# 3_Phase_Controller_V0_3.net
KiCad netlist of a schematic drawn in EAGLE
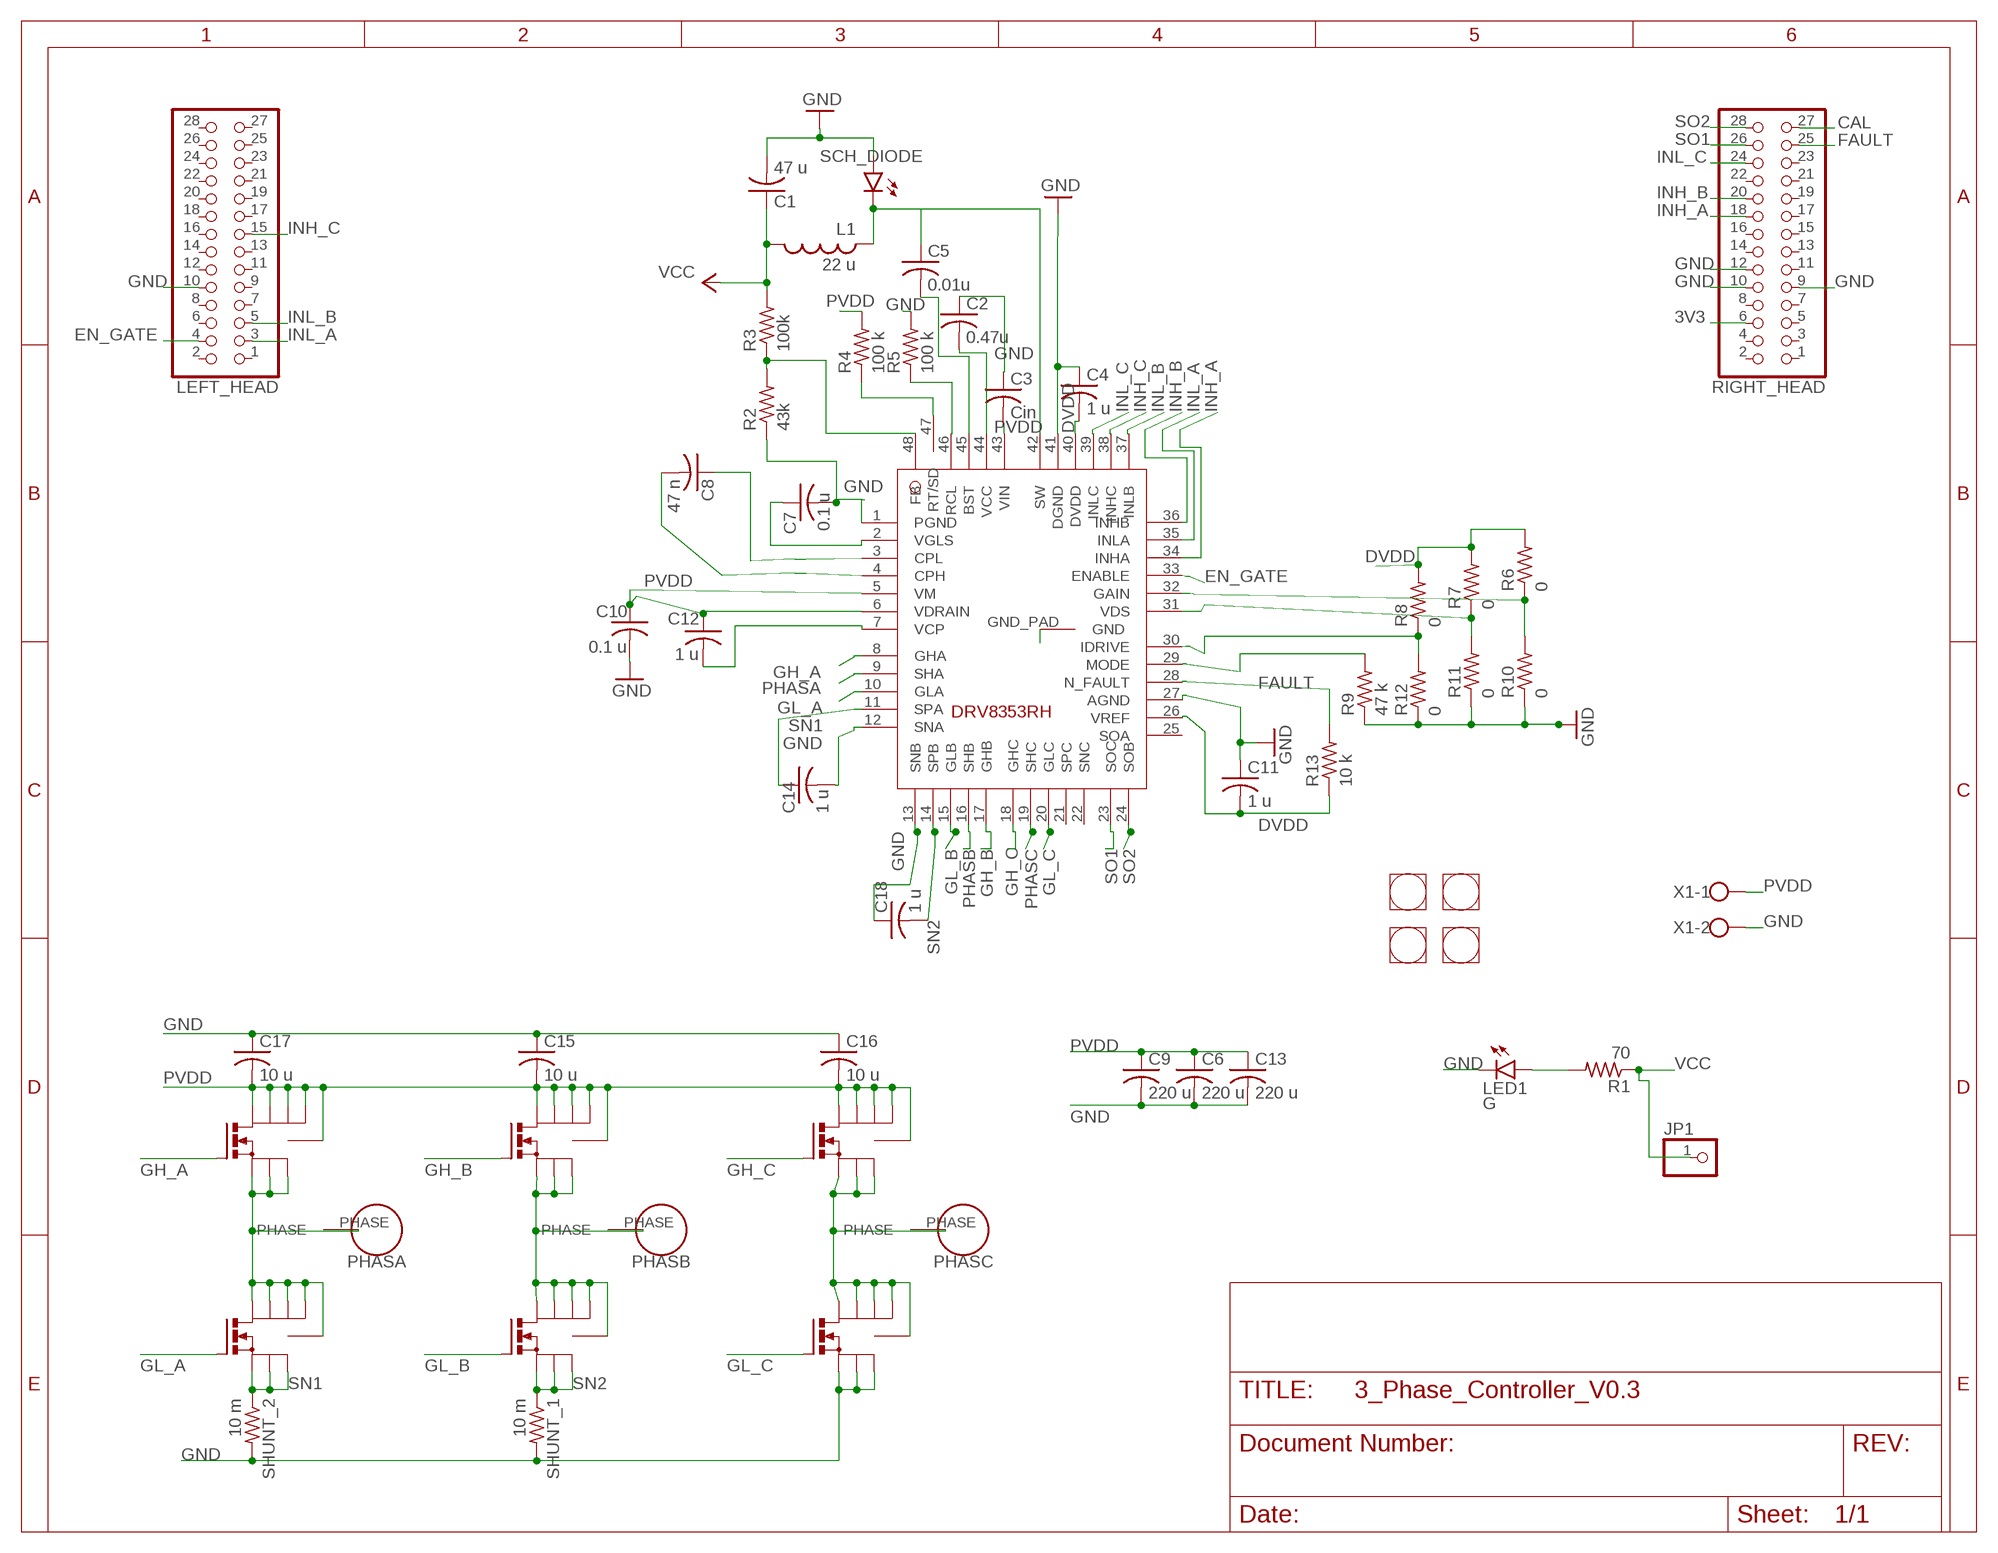
[diagram p0: schematic, sheet 1]

(export (version "E")
  (design (tool "Eeschema 10.0.6"))
  (components
    (comp (ref "A_H")
      (value "SIR178DP")
      (footprint "eagle-import:POWERPAK_SO-8_SINGLE")
      (libsource (lib "eagle-import") (part "SIR178DP"))
    )
    (comp (ref "A_L")
      (value "SIR178DP")
      (footprint "eagle-import:POWERPAK_SO-8_SINGLE")
      (libsource (lib "eagle-import") (part "SIR178DP"))
    )
    (comp (ref "B_H")
      (value "SIR178DP")
      (footprint "eagle-import:POWERPAK_SO-8_SINGLE")
      (libsource (lib "eagle-import") (part "SIR178DP"))
    )
    (comp (ref "B_L")
      (value "SIR178DP")
      (footprint "eagle-import:POWERPAK_SO-8_SINGLE")
      (libsource (lib "eagle-import") (part "SIR178DP"))
    )
    (comp (ref "C1")
      (value "47 u")
      (footprint "eagle-import:C025-024X044")
      (libsource (lib "eagle-import") (part "C-US025-024X044"))
    )
    (comp (ref "C2")
      (value "0.47u")
      (footprint "eagle-import:C0805")
      (libsource (lib "eagle-import") (part "C-USC0805"))
    )
    (comp (ref "C3")
      (value "Cin")
      (footprint "eagle-import:C0805")
      (libsource (lib "eagle-import") (part "C-USC0805"))
    )
    (comp (ref "C4")
      (value "1 u")
      (footprint "eagle-import:C0805")
      (libsource (lib "eagle-import") (part "C-USC0805"))
    )
    (comp (ref "C5")
      (value "0.01u")
      (footprint "eagle-import:C0805")
      (libsource (lib "eagle-import") (part "C-USC0805"))
    )
    (comp (ref "C6")
      (value "220 u")
      (footprint "eagle-import:C050-045X075")
      (libsource (lib "eagle-import") (part "C-US050-045X075"))
    )
    (comp (ref "C7")
      (value "0.1 u")
      (footprint "eagle-import:C0805")
      (libsource (lib "eagle-import") (part "C-USC0805"))
    )
    (comp (ref "C8")
      (value "47 n")
      (footprint "eagle-import:C0805")
      (libsource (lib "eagle-import") (part "C-USC0805"))
    )
    (comp (ref "C9")
      (value "220 u")
      (footprint "eagle-import:C050-045X075")
      (libsource (lib "eagle-import") (part "C-US050-045X075"))
    )
    (comp (ref "C10")
      (value "0.1 u")
      (footprint "eagle-import:C0805")
      (libsource (lib "eagle-import") (part "C-USC0805"))
    )
    (comp (ref "C11")
      (value "1 u")
      (footprint "eagle-import:C0805")
      (libsource (lib "eagle-import") (part "C-USC0805"))
    )
    (comp (ref "C12")
      (value "1 u")
      (footprint "eagle-import:C0805")
      (libsource (lib "eagle-import") (part "C-USC0805"))
    )
    (comp (ref "C13")
      (value "220 u")
      (footprint "eagle-import:C050-045X075")
      (libsource (lib "eagle-import") (part "C-US050-045X075"))
    )
    (comp (ref "C14")
      (value "1 u")
      (footprint "eagle-import:C0805")
      (libsource (lib "eagle-import") (part "C-USC0805"))
    )
    (comp (ref "C15")
      (value "10 u")
      (footprint "eagle-import:C1206")
      (libsource (lib "eagle-import") (part "C-USC1206"))
    )
    (comp (ref "C16")
      (value "10 u")
      (footprint "eagle-import:C1206")
      (libsource (lib "eagle-import") (part "C-USC1206"))
    )
    (comp (ref "C17")
      (value "10 u")
      (footprint "eagle-import:C1206")
      (libsource (lib "eagle-import") (part "C-USC1206"))
    )
    (comp (ref "C18")
      (value "1 u")
      (footprint "eagle-import:C0805")
      (libsource (lib "eagle-import") (part "C-USC0805"))
    )
    (comp (ref "C_H")
      (value "SIR178DP")
      (footprint "eagle-import:POWERPAK_SO-8_SINGLE")
      (libsource (lib "eagle-import") (part "SIR178DP"))
    )
    (comp (ref "C_L")
      (value "SIR178DP")
      (footprint "eagle-import:POWERPAK_SO-8_SINGLE")
      (libsource (lib "eagle-import") (part "SIR178DP"))
    )
    (comp (ref "JP1")
      (value "PINHD-1X1")
      (footprint "eagle-import:1X01")
      (libsource (lib "eagle-import") (part "PINHD-1X1"))
    )
    (comp (ref "L1")
      (value "22 u")
      (footprint "eagle-import:L3225M")
      (libsource (lib "eagle-import") (part "L-USL3225M"))
    )
    (comp (ref "LED1")
      (value "G")
      (footprint "eagle-import:SML0805")
      (libsource (lib "eagle-import") (part "LEDSML0805"))
    )
    (comp (ref "LEFT_HEAD")
      (value "PINHD-2X14")
      (footprint "eagle-import:2X14")
      (libsource (lib "eagle-import") (part "PINHD-2X14"))
    )
    (comp (ref "PHASE_A")
      (value "PHASE_HOLE_V_0.2")
      (footprint "eagle-import:HOLE_V_0.2")
      (libsource (lib "eagle-import") (part "PHASE_HOLE_V_0.2"))
    )
    (comp (ref "PHASE_B")
      (value "PHASE_HOLE_V_0.2")
      (footprint "eagle-import:HOLE_V_0.2")
      (libsource (lib "eagle-import") (part "PHASE_HOLE_V_0.2"))
    )
    (comp (ref "PHASE_C")
      (value "PHASE_HOLE_V_0.2")
      (footprint "eagle-import:HOLE_V_0.2")
      (libsource (lib "eagle-import") (part "PHASE_HOLE_V_0.2"))
    )
    (comp (ref "R1")
      (value "70")
      (footprint "eagle-import:R0805")
      (libsource (lib "eagle-import") (part "R-US_R0805"))
    )
    (comp (ref "R2")
      (value "43k")
      (footprint "eagle-import:R0603")
      (libsource (lib "eagle-import") (part "R-US_R0603"))
    )
    (comp (ref "R3")
      (value "100k")
      (footprint "eagle-import:R0603")
      (libsource (lib "eagle-import") (part "R-US_R0603"))
    )
    (comp (ref "R4")
      (value "100 k")
      (footprint "eagle-import:R0805")
      (libsource (lib "eagle-import") (part "R-US_R0805"))
    )
    (comp (ref "R5")
      (value "100 k")
      (footprint "eagle-import:R0805")
      (libsource (lib "eagle-import") (part "R-US_R0805"))
    )
    (comp (ref "R6")
      (value "0")
      (footprint "eagle-import:R0603")
      (libsource (lib "eagle-import") (part "R-US_R0603"))
    )
    (comp (ref "R7")
      (value "0")
      (footprint "eagle-import:R0603")
      (libsource (lib "eagle-import") (part "R-US_R0603"))
    )
    (comp (ref "R8")
      (value "0")
      (footprint "eagle-import:R0603")
      (libsource (lib "eagle-import") (part "R-US_R0603"))
    )
    (comp (ref "R9")
      (value "47 k")
      (footprint "eagle-import:R0603")
      (libsource (lib "eagle-import") (part "R-US_R0603"))
    )
    (comp (ref "R10")
      (value "0")
      (footprint "eagle-import:R0603")
      (libsource (lib "eagle-import") (part "R-US_R0603"))
    )
    (comp (ref "R11")
      (value "0")
      (footprint "eagle-import:R0603")
      (libsource (lib "eagle-import") (part "R-US_R0603"))
    )
    (comp (ref "R12")
      (value "0")
      (footprint "eagle-import:R0603")
      (libsource (lib "eagle-import") (part "R-US_R0603"))
    )
    (comp (ref "R13")
      (value "10 k")
      (footprint "eagle-import:R0603")
      (libsource (lib "eagle-import") (part "R-US_R0603"))
    )
    (comp (ref "RIGHT_HEAD")
      (value "PINHD-2X14")
      (footprint "eagle-import:2X14")
      (libsource (lib "eagle-import") (part "PINHD-2X14"))
    )
    (comp (ref "SCH_DIODE")
      (value "LEDCHIP-LED0805")
      (footprint "eagle-import:CHIP-LED0805")
      (libsource (lib "eagle-import") (part "LEDCHIP-LED0805"))
    )
    (comp (ref "SHUNT_1")
      (value "10 m")
      (footprint "eagle-import:R2512")
      (libsource (lib "eagle-import") (part "R-US_R2512"))
    )
    (comp (ref "SHUNT_2")
      (value "10 m")
      (footprint "eagle-import:R2512")
      (libsource (lib "eagle-import") (part "R-US_R2512"))
    )
    (comp (ref "U$1")
      (value "STANDOFF")
      (footprint "eagle-import:STANDOFF")
      (libsource (lib "eagle-import") (part "STANDOFF"))
    )
    (comp (ref "U$2")
      (value "STANDOFF")
      (footprint "eagle-import:STANDOFF")
      (libsource (lib "eagle-import") (part "STANDOFF"))
    )
    (comp (ref "U$3")
      (value "DRV8353RH")
      (footprint "eagle-import:VQFN-RGZ0048A")
      (libsource (lib "eagle-import") (part "DRV8353RH"))
    )
    (comp (ref "U$4")
      (value "STANDOFF")
      (footprint "eagle-import:STANDOFF")
      (libsource (lib "eagle-import") (part "STANDOFF"))
    )
    (comp (ref "U$5")
      (value "STANDOFF")
      (footprint "eagle-import:STANDOFF")
      (libsource (lib "eagle-import") (part "STANDOFF"))
    )
    (comp (ref "X1")
      (value "W237-102")
      (footprint "eagle-import:W237-102")
      (fields (field (name "MPN") "237-102"))
      (libsource (lib "eagle-import") (part "W237-102"))
    )
  )
  (nets
    (net (code "1") (name "/3V3") (class "Default")
      (node (ref "RIGHT_HEAD") (pin "6") (pinfunction "6_6") (pintype "passive"))
    )
    (net (code "2") (name "/CAL") (class "Default")
      (node (ref "RIGHT_HEAD") (pin "27") (pinfunction "27_27") (pintype "passive"))
    )
    (net (code "3") (name "/DVDD") (class "Default")
      (node (ref "C11") (pin "2") (pinfunction "2_2") (pintype "passive"))
      (node (ref "C4") (pin "2") (pinfunction "2_2") (pintype "passive"))
      (node (ref "R13") (pin "1") (pinfunction "1_1") (pintype "passive"))
      (node (ref "R6") (pin "2") (pinfunction "2_2") (pintype "passive"))
      (node (ref "R7") (pin "2") (pinfunction "2_2") (pintype "passive"))
      (node (ref "R8") (pin "2") (pinfunction "2_2") (pintype "passive"))
      (node (ref "U$3") (pin "26") (pinfunction "VREF_26") (pintype "bidirectional"))
      (node (ref "U$3") (pin "40") (pinfunction "DVDD_40") (pintype "bidirectional"))
    )
    (net (code "4") (name "/EN_GATE") (class "Default")
      (node (ref "LEFT_HEAD") (pin "4") (pinfunction "4_4") (pintype "passive"))
      (node (ref "U$3") (pin "33") (pinfunction "ENABLE_33") (pintype "bidirectional"))
    )
    (net (code "5") (name "/FAULT") (class "Default")
      (node (ref "R13") (pin "2") (pinfunction "2_2") (pintype "passive"))
      (node (ref "RIGHT_HEAD") (pin "25") (pinfunction "25_25") (pintype "passive"))
      (node (ref "U$3") (pin "28") (pinfunction "N_FAULT_28") (pintype "bidirectional"))
    )
    (net (code "6") (name "/GH_A") (class "Default")
      (node (ref "A_H") (pin "GATE") (pinfunction "G_GATE") (pintype "passive"))
      (node (ref "U$3") (pin "8") (pinfunction "GHA_8") (pintype "bidirectional"))
    )
    (net (code "7") (name "/GH_B") (class "Default")
      (node (ref "B_H") (pin "GATE") (pinfunction "G_GATE") (pintype "passive"))
      (node (ref "U$3") (pin "17") (pinfunction "GHB_17") (pintype "bidirectional"))
    )
    (net (code "8") (name "/GH_C") (class "Default")
      (node (ref "C_H") (pin "GATE") (pinfunction "G_GATE") (pintype "passive"))
      (node (ref "U$3") (pin "18") (pinfunction "GHC_18") (pintype "bidirectional"))
    )
    (net (code "9") (name "/GL_A") (class "Default")
      (node (ref "A_L") (pin "GATE") (pinfunction "G_GATE") (pintype "passive"))
      (node (ref "U$3") (pin "10") (pinfunction "GLA_10") (pintype "bidirectional"))
    )
    (net (code "10") (name "/GL_B") (class "Default")
      (node (ref "B_L") (pin "GATE") (pinfunction "G_GATE") (pintype "passive"))
      (node (ref "U$3") (pin "15") (pinfunction "GLB_15") (pintype "bidirectional"))
    )
    (net (code "11") (name "/GL_C") (class "Default")
      (node (ref "C_L") (pin "GATE") (pinfunction "G_GATE") (pintype "passive"))
      (node (ref "U$3") (pin "20") (pinfunction "GLC_20") (pintype "bidirectional"))
    )
    (net (code "12") (name "/INH_A") (class "Default")
      (node (ref "RIGHT_HEAD") (pin "18") (pinfunction "18_18") (pintype "passive"))
      (node (ref "U$3") (pin "34") (pinfunction "INHA_34") (pintype "bidirectional"))
    )
    (net (code "13") (name "/INH_B") (class "Default")
      (node (ref "RIGHT_HEAD") (pin "20") (pinfunction "20_20") (pintype "passive"))
      (node (ref "U$3") (pin "36") (pinfunction "INHB_36") (pintype "bidirectional"))
    )
    (net (code "14") (name "/INH_C") (class "Default")
      (node (ref "LEFT_HEAD") (pin "15") (pinfunction "15_15") (pintype "passive"))
      (node (ref "U$3") (pin "38") (pinfunction "INHC_38") (pintype "bidirectional"))
    )
    (net (code "15") (name "/INL_A") (class "Default")
      (node (ref "LEFT_HEAD") (pin "3") (pinfunction "3_3") (pintype "passive"))
      (node (ref "U$3") (pin "35") (pinfunction "INLA_35") (pintype "bidirectional"))
    )
    (net (code "16") (name "/INL_B") (class "Default")
      (node (ref "LEFT_HEAD") (pin "5") (pinfunction "5_5") (pintype "passive"))
      (node (ref "U$3") (pin "37") (pinfunction "INLB_37") (pintype "bidirectional"))
    )
    (net (code "17") (name "/INL_C") (class "Default")
      (node (ref "RIGHT_HEAD") (pin "24") (pinfunction "24_24") (pintype "passive"))
      (node (ref "U$3") (pin "39") (pinfunction "INLC_39") (pintype "bidirectional"))
    )
    (net (code "18") (name "/PHASA") (class "Default")
      (node (ref "A_H") (pin "S_1") (pinfunction "S_S_1") (pintype "passive"))
      (node (ref "A_H") (pin "S_2") (pinfunction "S1_S_2") (pintype "passive"))
      (node (ref "A_H") (pin "S_3") (pinfunction "S2_S_3") (pintype "passive"))
      (node (ref "A_L") (pin "D_1") (pinfunction "D_D_1") (pintype "passive"))
      (node (ref "A_L") (pin "D_2") (pinfunction "D1_D_2") (pintype "passive"))
      (node (ref "A_L") (pin "D_3") (pinfunction "D2_D_3") (pintype "passive"))
      (node (ref "A_L") (pin "D_4") (pinfunction "D3_D_4") (pintype "passive"))
      (node (ref "A_L") (pin "THRM") (pinfunction "THERMAL_THRM") (pintype "passive"))
      (node (ref "PHASE_A") (pin "PHASE") (pinfunction "PHASE_PHASE") (pintype "bidirectional"))
      (node (ref "U$3") (pin "9") (pinfunction "SHA_9") (pintype "bidirectional"))
    )
    (net (code "19") (name "/PHASB") (class "Default")
      (node (ref "B_H") (pin "S_1") (pinfunction "S_S_1") (pintype "passive"))
      (node (ref "B_H") (pin "S_2") (pinfunction "S1_S_2") (pintype "passive"))
      (node (ref "B_H") (pin "S_3") (pinfunction "S2_S_3") (pintype "passive"))
      (node (ref "B_L") (pin "D_1") (pinfunction "D_D_1") (pintype "passive"))
      (node (ref "B_L") (pin "D_2") (pinfunction "D1_D_2") (pintype "passive"))
      (node (ref "B_L") (pin "D_3") (pinfunction "D2_D_3") (pintype "passive"))
      (node (ref "B_L") (pin "D_4") (pinfunction "D3_D_4") (pintype "passive"))
      (node (ref "B_L") (pin "THRM") (pinfunction "THERMAL_THRM") (pintype "passive"))
      (node (ref "PHASE_B") (pin "PHASE") (pinfunction "PHASE_PHASE") (pintype "bidirectional"))
      (node (ref "U$3") (pin "16") (pinfunction "SHB_16") (pintype "bidirectional"))
    )
    (net (code "20") (name "/PHASC") (class "Default")
      (node (ref "C_H") (pin "S_1") (pinfunction "S_S_1") (pintype "passive"))
      (node (ref "C_H") (pin "S_2") (pinfunction "S1_S_2") (pintype "passive"))
      (node (ref "C_H") (pin "S_3") (pinfunction "S2_S_3") (pintype "passive"))
      (node (ref "C_L") (pin "D_1") (pinfunction "D_D_1") (pintype "passive"))
      (node (ref "C_L") (pin "D_2") (pinfunction "D1_D_2") (pintype "passive"))
      (node (ref "C_L") (pin "D_3") (pinfunction "D2_D_3") (pintype "passive"))
      (node (ref "C_L") (pin "D_4") (pinfunction "D3_D_4") (pintype "passive"))
      (node (ref "C_L") (pin "THRM") (pinfunction "THERMAL_THRM") (pintype "passive"))
      (node (ref "PHASE_C") (pin "PHASE") (pinfunction "PHASE_PHASE") (pintype "bidirectional"))
      (node (ref "U$3") (pin "19") (pinfunction "SHC_19") (pintype "bidirectional"))
    )
    (net (code "21") (name "/PVDD") (class "Default")
      (node (ref "A_H") (pin "D_1") (pinfunction "D_D_1") (pintype "passive"))
      (node (ref "A_H") (pin "D_2") (pinfunction "D1_D_2") (pintype "passive"))
      (node (ref "A_H") (pin "D_3") (pinfunction "D2_D_3") (pintype "passive"))
      (node (ref "A_H") (pin "D_4") (pinfunction "D3_D_4") (pintype "passive"))
      (node (ref "A_H") (pin "THRM") (pinfunction "THERMAL_THRM") (pintype "passive"))
      (node (ref "B_H") (pin "D_1") (pinfunction "D_D_1") (pintype "passive"))
      (node (ref "B_H") (pin "D_2") (pinfunction "D1_D_2") (pintype "passive"))
      (node (ref "B_H") (pin "D_3") (pinfunction "D2_D_3") (pintype "passive"))
      (node (ref "B_H") (pin "D_4") (pinfunction "D3_D_4") (pintype "passive"))
      (node (ref "B_H") (pin "THRM") (pinfunction "THERMAL_THRM") (pintype "passive"))
      (node (ref "C10") (pin "1") (pinfunction "1_1") (pintype "passive"))
      (node (ref "C12") (pin "1") (pinfunction "1_1") (pintype "passive"))
      (node (ref "C13") (pin "1") (pinfunction "1_1") (pintype "passive"))
      (node (ref "C15") (pin "2") (pinfunction "2_2") (pintype "passive"))
      (node (ref "C16") (pin "2") (pinfunction "2_2") (pintype "passive"))
      (node (ref "C17") (pin "2") (pinfunction "2_2") (pintype "passive"))
      (node (ref "C3") (pin "2") (pinfunction "2_2") (pintype "passive"))
      (node (ref "C6") (pin "1") (pinfunction "1_1") (pintype "passive"))
      (node (ref "C9") (pin "1") (pinfunction "1_1") (pintype "passive"))
      (node (ref "C_H") (pin "D_1") (pinfunction "D_D_1") (pintype "passive"))
      (node (ref "C_H") (pin "D_2") (pinfunction "D1_D_2") (pintype "passive"))
      (node (ref "C_H") (pin "D_3") (pinfunction "D2_D_3") (pintype "passive"))
      (node (ref "C_H") (pin "D_4") (pinfunction "D3_D_4") (pintype "passive"))
      (node (ref "C_H") (pin "THRM") (pinfunction "THERMAL_THRM") (pintype "passive"))
      (node (ref "R4") (pin "2") (pinfunction "2_2") (pintype "passive"))
      (node (ref "U$3") (pin "43") (pinfunction "VIN_43") (pintype "bidirectional"))
      (node (ref "U$3") (pin "5") (pinfunction "VM_5") (pintype "bidirectional"))
      (node (ref "U$3") (pin "6") (pinfunction "VDRAIN_6") (pintype "bidirectional"))
      (node (ref "X1") (pin "1") (pinfunction "KL_1") (pintype "passive"))
    )
    (net (code "22") (name "/SN1") (class "Default")
      (node (ref "A_L") (pin "S_1") (pinfunction "S_S_1") (pintype "passive"))
      (node (ref "A_L") (pin "S_2") (pinfunction "S1_S_2") (pintype "passive"))
      (node (ref "A_L") (pin "S_3") (pinfunction "S2_S_3") (pintype "passive"))
      (node (ref "C14") (pin "1") (pinfunction "1_1") (pintype "passive"))
      (node (ref "SHUNT_2") (pin "1") (pinfunction "1_1") (pintype "passive"))
      (node (ref "U$3") (pin "11") (pinfunction "SPA_11") (pintype "bidirectional"))
    )
    (net (code "23") (name "/SN2") (class "Default")
      (node (ref "B_L") (pin "S_1") (pinfunction "S_S_1") (pintype "passive"))
      (node (ref "B_L") (pin "S_2") (pinfunction "S1_S_2") (pintype "passive"))
      (node (ref "B_L") (pin "S_3") (pinfunction "S2_S_3") (pintype "passive"))
      (node (ref "C18") (pin "2") (pinfunction "2_2") (pintype "passive"))
      (node (ref "SHUNT_1") (pin "1") (pinfunction "1_1") (pintype "passive"))
      (node (ref "U$3") (pin "14") (pinfunction "SPB_14") (pintype "bidirectional"))
    )
    (net (code "24") (name "/SO1") (class "Default")
      (node (ref "RIGHT_HEAD") (pin "26") (pinfunction "26_26") (pintype "passive"))
      (node (ref "U$3") (pin "23") (pinfunction "SOC_23") (pintype "bidirectional"))
    )
    (net (code "25") (name "/SO2") (class "Default")
      (node (ref "RIGHT_HEAD") (pin "28") (pinfunction "28_28") (pintype "passive"))
      (node (ref "U$3") (pin "24") (pinfunction "SOB_24") (pintype "bidirectional"))
    )
    (net (code "26") (name "GND") (class "Default")
      (node (ref "C1") (pin "2") (pinfunction "2_2") (pintype "passive"))
      (node (ref "C10") (pin "2") (pinfunction "2_2") (pintype "passive"))
      (node (ref "C11") (pin "1") (pinfunction "1_1") (pintype "passive"))
      (node (ref "C13") (pin "2") (pinfunction "2_2") (pintype "passive"))
      (node (ref "C14") (pin "2") (pinfunction "2_2") (pintype "passive"))
      (node (ref "C15") (pin "1") (pinfunction "1_1") (pintype "passive"))
      (node (ref "C16") (pin "1") (pinfunction "1_1") (pintype "passive"))
      (node (ref "C17") (pin "1") (pinfunction "1_1") (pintype "passive"))
      (node (ref "C18") (pin "1") (pinfunction "1_1") (pintype "passive"))
      (node (ref "C2") (pin "1") (pinfunction "1_1") (pintype "passive"))
      (node (ref "C3") (pin "1") (pinfunction "1_1") (pintype "passive"))
      (node (ref "C4") (pin "1") (pinfunction "1_1") (pintype "passive"))
      (node (ref "C6") (pin "2") (pinfunction "2_2") (pintype "passive"))
      (node (ref "C7") (pin "2") (pinfunction "2_2") (pintype "passive"))
      (node (ref "C9") (pin "2") (pinfunction "2_2") (pintype "passive"))
      (node (ref "C_L") (pin "S_1") (pinfunction "S_S_1") (pintype "passive"))
      (node (ref "C_L") (pin "S_2") (pinfunction "S1_S_2") (pintype "passive"))
      (node (ref "C_L") (pin "S_3") (pinfunction "S2_S_3") (pintype "passive"))
      (node (ref "LED1") (pin "C") (pinfunction "C_C") (pintype "passive"))
      (node (ref "LEFT_HEAD") (pin "10") (pinfunction "10_10") (pintype "passive"))
      (node (ref "R10") (pin "1") (pinfunction "1_1") (pintype "passive"))
      (node (ref "R11") (pin "1") (pinfunction "1_1") (pintype "passive"))
      (node (ref "R12") (pin "1") (pinfunction "1_1") (pintype "passive"))
      (node (ref "R2") (pin "1") (pinfunction "1_1") (pintype "passive"))
      (node (ref "R5") (pin "2") (pinfunction "2_2") (pintype "passive"))
      (node (ref "R9") (pin "1") (pinfunction "1_1") (pintype "passive"))
      (node (ref "RIGHT_HEAD") (pin "10") (pinfunction "10_10") (pintype "passive"))
      (node (ref "RIGHT_HEAD") (pin "12") (pinfunction "12_12") (pintype "passive"))
      (node (ref "RIGHT_HEAD") (pin "9") (pinfunction "9_9") (pintype "passive"))
      (node (ref "SCH_DIODE") (pin "A") (pinfunction "A_A") (pintype "passive"))
      (node (ref "SHUNT_1") (pin "2") (pinfunction "2_2") (pintype "passive"))
      (node (ref "SHUNT_2") (pin "2") (pinfunction "2_2") (pintype "passive"))
      (node (ref "U$3") (pin "1") (pinfunction "PGND_1") (pintype "bidirectional"))
      (node (ref "U$3") (pin "12") (pinfunction "SNA_12") (pintype "bidirectional"))
      (node (ref "U$3") (pin "13") (pinfunction "SNB_13") (pintype "bidirectional"))
      (node (ref "U$3") (pin "27") (pinfunction "AGND_27") (pintype "bidirectional"))
      (node (ref "U$3") (pin "41") (pinfunction "DGND_41") (pintype "bidirectional"))
      (node (ref "U$3") (pin "GND_PAD") (pinfunction "GND_GND_PAD") (pintype "bidirectional"))
      (node (ref "X1") (pin "2") (pinfunction "KL_2") (pintype "passive"))
    )
    (net (code "27") (name "Net-(LED1-PadA)") (class "Default")
      (node (ref "LED1") (pin "A") (pinfunction "A_A") (pintype "passive"))
      (node (ref "R1") (pin "2") (pinfunction "2_2") (pintype "passive"))
    )
    (net (code "28") (name "Net-(U$3-BST)") (class "Default")
      (node (ref "C5") (pin "2") (pinfunction "2_2") (pintype "passive"))
      (node (ref "U$3") (pin "45") (pinfunction "BST_45") (pintype "bidirectional"))
    )
    (net (code "29") (name "Net-(U$3-CPH)") (class "Default")
      (node (ref "C8") (pin "2") (pinfunction "2_2") (pintype "passive"))
      (node (ref "U$3") (pin "4") (pinfunction "CPH_4") (pintype "bidirectional"))
    )
    (net (code "30") (name "Net-(U$3-CPL)") (class "Default")
      (node (ref "C8") (pin "1") (pinfunction "1_1") (pintype "passive"))
      (node (ref "U$3") (pin "3") (pinfunction "CPL_3") (pintype "bidirectional"))
    )
    (net (code "31") (name "Net-(U$3-FB)") (class "Default")
      (node (ref "R2") (pin "2") (pinfunction "2_2") (pintype "passive"))
      (node (ref "R3") (pin "1") (pinfunction "1_1") (pintype "passive"))
      (node (ref "U$3") (pin "48") (pinfunction "FB_48") (pintype "bidirectional"))
    )
    (net (code "32") (name "Net-(U$3-GAIN)") (class "Default")
      (node (ref "R10") (pin "2") (pinfunction "2_2") (pintype "passive"))
      (node (ref "R6") (pin "1") (pinfunction "1_1") (pintype "passive"))
      (node (ref "U$3") (pin "32") (pinfunction "GAIN_32") (pintype "bidirectional"))
    )
    (net (code "33") (name "Net-(U$3-IDRIVE)") (class "Default")
      (node (ref "R12") (pin "2") (pinfunction "2_2") (pintype "passive"))
      (node (ref "R8") (pin "1") (pinfunction "1_1") (pintype "passive"))
      (node (ref "U$3") (pin "30") (pinfunction "IDRIVE_30") (pintype "bidirectional"))
    )
    (net (code "34") (name "Net-(U$3-MODE)") (class "Default")
      (node (ref "R9") (pin "2") (pinfunction "2_2") (pintype "passive"))
      (node (ref "U$3") (pin "29") (pinfunction "MODE_29") (pintype "bidirectional"))
    )
    (net (code "35") (name "Net-(U$3-RCL)") (class "Default")
      (node (ref "R5") (pin "1") (pinfunction "1_1") (pintype "passive"))
      (node (ref "U$3") (pin "46") (pinfunction "RCL_46") (pintype "bidirectional"))
    )
    (net (code "36") (name "Net-(U$3-RT{slash}SD)") (class "Default")
      (node (ref "R4") (pin "1") (pinfunction "1_1") (pintype "passive"))
      (node (ref "U$3") (pin "47") (pinfunction "RT/SD_47") (pintype "bidirectional"))
    )
    (net (code "37") (name "Net-(U$3-SW)") (class "Default")
      (node (ref "C5") (pin "1") (pinfunction "1_1") (pintype "passive"))
      (node (ref "L1") (pin "2") (pinfunction "2_2") (pintype "passive"))
      (node (ref "SCH_DIODE") (pin "C") (pinfunction "C_C") (pintype "passive"))
      (node (ref "U$3") (pin "42") (pinfunction "SW_42") (pintype "bidirectional"))
    )
    (net (code "38") (name "Net-(U$3-VCC)") (class "Default")
      (node (ref "C2") (pin "2") (pinfunction "2_2") (pintype "passive"))
      (node (ref "U$3") (pin "44") (pinfunction "VCC_44") (pintype "bidirectional"))
    )
    (net (code "39") (name "Net-(U$3-VCP)") (class "Default")
      (node (ref "C12") (pin "2") (pinfunction "2_2") (pintype "passive"))
      (node (ref "U$3") (pin "7") (pinfunction "VCP_7") (pintype "bidirectional"))
    )
    (net (code "40") (name "Net-(U$3-VDS)") (class "Default")
      (node (ref "R11") (pin "2") (pinfunction "2_2") (pintype "passive"))
      (node (ref "R7") (pin "1") (pinfunction "1_1") (pintype "passive"))
      (node (ref "U$3") (pin "31") (pinfunction "VDS_31") (pintype "bidirectional"))
    )
    (net (code "41") (name "Net-(U$3-VGLS)") (class "Default")
      (node (ref "C7") (pin "1") (pinfunction "1_1") (pintype "passive"))
      (node (ref "U$3") (pin "2") (pinfunction "VGLS_2") (pintype "bidirectional"))
    )
    (net (code "42") (name "VCC") (class "Default")
      (node (ref "C1") (pin "1") (pinfunction "1_1") (pintype "passive"))
      (node (ref "JP1") (pin "1") (pinfunction "1_1") (pintype "passive"))
      (node (ref "L1") (pin "1") (pinfunction "1_1") (pintype "passive"))
      (node (ref "R1") (pin "1") (pinfunction "1_1") (pintype "passive"))
      (node (ref "R3") (pin "2") (pinfunction "2_2") (pintype "passive"))
    )
    (net (code "43") (name "unconnected-(LEFT_HEAD-Pad1)") (class "Default")
      (node (ref "LEFT_HEAD") (pin "1") (pinfunction "1_1") (pintype "passive"))
    )
    (net (code "44") (name "unconnected-(LEFT_HEAD-Pad2)") (class "Default")
      (node (ref "LEFT_HEAD") (pin "2") (pinfunction "2_2") (pintype "passive"))
    )
    (net (code "45") (name "unconnected-(LEFT_HEAD-Pad6)") (class "Default")
      (node (ref "LEFT_HEAD") (pin "6") (pinfunction "6_6") (pintype "passive"))
    )
    (net (code "46") (name "unconnected-(LEFT_HEAD-Pad7)") (class "Default")
      (node (ref "LEFT_HEAD") (pin "7") (pinfunction "7_7") (pintype "passive"))
    )
    (net (code "47") (name "unconnected-(LEFT_HEAD-Pad8)") (class "Default")
      (node (ref "LEFT_HEAD") (pin "8") (pinfunction "8_8") (pintype "passive"))
    )
    (net (code "48") (name "unconnected-(LEFT_HEAD-Pad9)") (class "Default")
      (node (ref "LEFT_HEAD") (pin "9") (pinfunction "9_9") (pintype "passive"))
    )
    (net (code "49") (name "unconnected-(LEFT_HEAD-Pad11)") (class "Default")
      (node (ref "LEFT_HEAD") (pin "11") (pinfunction "11_11") (pintype "passive"))
    )
    (net (code "50") (name "unconnected-(LEFT_HEAD-Pad12)") (class "Default")
      (node (ref "LEFT_HEAD") (pin "12") (pinfunction "12_12") (pintype "passive"))
    )
    (net (code "51") (name "unconnected-(LEFT_HEAD-Pad13)") (class "Default")
      (node (ref "LEFT_HEAD") (pin "13") (pinfunction "13_13") (pintype "passive"))
    )
    (net (code "52") (name "unconnected-(LEFT_HEAD-Pad14)") (class "Default")
      (node (ref "LEFT_HEAD") (pin "14") (pinfunction "14_14") (pintype "passive"))
    )
    (net (code "53") (name "unconnected-(LEFT_HEAD-Pad16)") (class "Default")
      (node (ref "LEFT_HEAD") (pin "16") (pinfunction "16_16") (pintype "passive"))
    )
    (net (code "54") (name "unconnected-(LEFT_HEAD-Pad17)") (class "Default")
      (node (ref "LEFT_HEAD") (pin "17") (pinfunction "17_17") (pintype "passive"))
    )
    (net (code "55") (name "unconnected-(LEFT_HEAD-Pad18)") (class "Default")
      (node (ref "LEFT_HEAD") (pin "18") (pinfunction "18_18") (pintype "passive"))
    )
    (net (code "56") (name "unconnected-(LEFT_HEAD-Pad19)") (class "Default")
      (node (ref "LEFT_HEAD") (pin "19") (pinfunction "19_19") (pintype "passive"))
    )
    (net (code "57") (name "unconnected-(LEFT_HEAD-Pad20)") (class "Default")
      (node (ref "LEFT_HEAD") (pin "20") (pinfunction "20_20") (pintype "passive"))
    )
    (net (code "58") (name "unconnected-(LEFT_HEAD-Pad21)") (class "Default")
      (node (ref "LEFT_HEAD") (pin "21") (pinfunction "21_21") (pintype "passive"))
    )
    (net (code "59") (name "unconnected-(LEFT_HEAD-Pad22)") (class "Default")
      (node (ref "LEFT_HEAD") (pin "22") (pinfunction "22_22") (pintype "passive"))
    )
    (net (code "60") (name "unconnected-(LEFT_HEAD-Pad23)") (class "Default")
      (node (ref "LEFT_HEAD") (pin "23") (pinfunction "23_23") (pintype "passive"))
    )
    (net (code "61") (name "unconnected-(LEFT_HEAD-Pad24)") (class "Default")
      (node (ref "LEFT_HEAD") (pin "24") (pinfunction "24_24") (pintype "passive"))
    )
    (net (code "62") (name "unconnected-(LEFT_HEAD-Pad25)") (class "Default")
      (node (ref "LEFT_HEAD") (pin "25") (pinfunction "25_25") (pintype "passive"))
    )
    (net (code "63") (name "unconnected-(LEFT_HEAD-Pad26)") (class "Default")
      (node (ref "LEFT_HEAD") (pin "26") (pinfunction "26_26") (pintype "passive"))
    )
    (net (code "64") (name "unconnected-(LEFT_HEAD-Pad27)") (class "Default")
      (node (ref "LEFT_HEAD") (pin "27") (pinfunction "27_27") (pintype "passive"))
    )
    (net (code "65") (name "unconnected-(LEFT_HEAD-Pad28)") (class "Default")
      (node (ref "LEFT_HEAD") (pin "28") (pinfunction "28_28") (pintype "passive"))
    )
    (net (code "66") (name "unconnected-(RIGHT_HEAD-Pad1)") (class "Default")
      (node (ref "RIGHT_HEAD") (pin "1") (pinfunction "1_1") (pintype "passive"))
    )
    (net (code "67") (name "unconnected-(RIGHT_HEAD-Pad2)") (class "Default")
      (node (ref "RIGHT_HEAD") (pin "2") (pinfunction "2_2") (pintype "passive"))
    )
    (net (code "68") (name "unconnected-(RIGHT_HEAD-Pad3)") (class "Default")
      (node (ref "RIGHT_HEAD") (pin "3") (pinfunction "3_3") (pintype "passive"))
    )
    (net (code "69") (name "unconnected-(RIGHT_HEAD-Pad4)") (class "Default")
      (node (ref "RIGHT_HEAD") (pin "4") (pinfunction "4_4") (pintype "passive"))
    )
    (net (code "70") (name "unconnected-(RIGHT_HEAD-Pad5)") (class "Default")
      (node (ref "RIGHT_HEAD") (pin "5") (pinfunction "5_5") (pintype "passive"))
    )
    (net (code "71") (name "unconnected-(RIGHT_HEAD-Pad7)") (class "Default")
      (node (ref "RIGHT_HEAD") (pin "7") (pinfunction "7_7") (pintype "passive"))
    )
    (net (code "72") (name "unconnected-(RIGHT_HEAD-Pad8)") (class "Default")
      (node (ref "RIGHT_HEAD") (pin "8") (pinfunction "8_8") (pintype "passive"))
    )
    (net (code "73") (name "unconnected-(RIGHT_HEAD-Pad11)") (class "Default")
      (node (ref "RIGHT_HEAD") (pin "11") (pinfunction "11_11") (pintype "passive"))
    )
    (net (code "74") (name "unconnected-(RIGHT_HEAD-Pad13)") (class "Default")
      (node (ref "RIGHT_HEAD") (pin "13") (pinfunction "13_13") (pintype "passive"))
    )
    (net (code "75") (name "unconnected-(RIGHT_HEAD-Pad14)") (class "Default")
      (node (ref "RIGHT_HEAD") (pin "14") (pinfunction "14_14") (pintype "passive"))
    )
    (net (code "76") (name "unconnected-(RIGHT_HEAD-Pad15)") (class "Default")
      (node (ref "RIGHT_HEAD") (pin "15") (pinfunction "15_15") (pintype "passive"))
    )
    (net (code "77") (name "unconnected-(RIGHT_HEAD-Pad16)") (class "Default")
      (node (ref "RIGHT_HEAD") (pin "16") (pinfunction "16_16") (pintype "passive"))
    )
    (net (code "78") (name "unconnected-(RIGHT_HEAD-Pad17)") (class "Default")
      (node (ref "RIGHT_HEAD") (pin "17") (pinfunction "17_17") (pintype "passive"))
    )
    (net (code "79") (name "unconnected-(RIGHT_HEAD-Pad19)") (class "Default")
      (node (ref "RIGHT_HEAD") (pin "19") (pinfunction "19_19") (pintype "passive"))
    )
    (net (code "80") (name "unconnected-(RIGHT_HEAD-Pad21)") (class "Default")
      (node (ref "RIGHT_HEAD") (pin "21") (pinfunction "21_21") (pintype "passive"))
    )
    (net (code "81") (name "unconnected-(RIGHT_HEAD-Pad22)") (class "Default")
      (node (ref "RIGHT_HEAD") (pin "22") (pinfunction "22_22") (pintype "passive"))
    )
    (net (code "82") (name "unconnected-(RIGHT_HEAD-Pad23)") (class "Default")
      (node (ref "RIGHT_HEAD") (pin "23") (pinfunction "23_23") (pintype "passive"))
    )
    (net (code "83") (name "unconnected-(U$3-SNC-Pad22)") (class "Default")
      (node (ref "U$3") (pin "22") (pinfunction "SNC_22") (pintype "bidirectional"))
    )
    (net (code "84") (name "unconnected-(U$3-SOA-Pad25)") (class "Default")
      (node (ref "U$3") (pin "25") (pinfunction "SOA_25") (pintype "bidirectional"))
    )
    (net (code "85") (name "unconnected-(U$3-SPC-Pad21)") (class "Default")
      (node (ref "U$3") (pin "21") (pinfunction "SPC_21") (pintype "bidirectional"))
    )
  )
)
